# realSchematic.net
KiCad netlist of a schematic drawn in Altium Designer
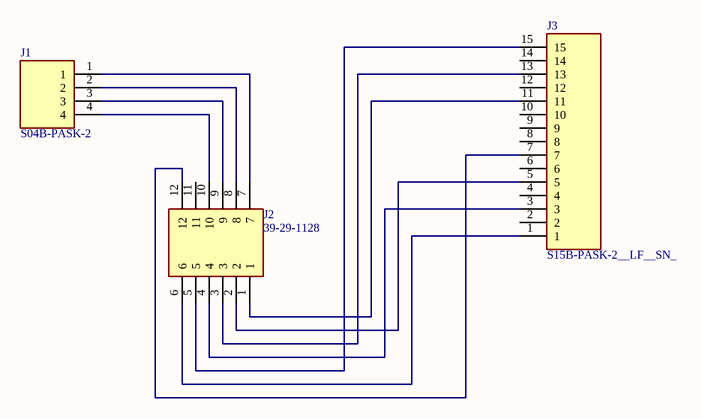
[diagram p0: realSchematic.SchDoc]

(export (version "E")
  (design (tool "Eeschema 10.0.6"))
  (components
    (comp (ref "J1")
      (value "S04B-PASK-2")
      (footprint "SamacSys:S04BPASK2")
      (description "Connector")
      (libsource (lib "*") (part "S04B-PASK-2"))
    )
    (comp (ref "J2")
      (value "39-29-1128")
      (footprint "SamacSys:39291128")
      (description "Connector")
      (fields (field (name "MOUSER PART NUMBER") "538-39-29-1128"))
      (libsource (lib "*") (part "39-29-1128"))
    )
    (comp (ref "J3")
      (value "S15B-PASK-2__LF__SN_")
      (footprint "SamacSys:S15BPASK2LFSN")
      (description "Connector")
      (fields (field (name "MANUFACTURER_PART_NUMBER") "S15B-PASK-2 (LF)(SN)"))
      (libsource (lib "*") (part "S15B-PASK-2__LF__SN_"))
    )
  )
  (nets
    (net (code "1") (name "Net-(J1-Pad1)") (class "Default")
      (node (ref "J1") (pin "1") (pinfunction "1_1") (pintype "passive"))
      (node (ref "J2") (pin "7") (pinfunction "7_7") (pintype "passive"))
    )
    (net (code "2") (name "Net-(J1-Pad2)") (class "Default")
      (node (ref "J1") (pin "2") (pinfunction "2_2") (pintype "passive"))
      (node (ref "J2") (pin "8") (pinfunction "8_8") (pintype "passive"))
    )
    (net (code "3") (name "Net-(J1-Pad3)") (class "Default")
      (node (ref "J1") (pin "3") (pinfunction "3_3") (pintype "passive"))
      (node (ref "J2") (pin "9") (pinfunction "9_9") (pintype "passive"))
    )
    (net (code "4") (name "Net-(J1-Pad4)") (class "Default")
      (node (ref "J1") (pin "4") (pinfunction "4_4") (pintype "passive"))
      (node (ref "J2") (pin "10") (pinfunction "10_10") (pintype "passive"))
    )
    (net (code "5") (name "Net-(J2-Pad1)") (class "Default")
      (node (ref "J2") (pin "1") (pinfunction "1_1") (pintype "passive"))
      (node (ref "J3") (pin "11") (pinfunction "11_11") (pintype "passive"))
    )
    (net (code "6") (name "Net-(J2-Pad2)") (class "Default")
      (node (ref "J2") (pin "2") (pinfunction "2_2") (pintype "passive"))
      (node (ref "J3") (pin "5") (pinfunction "5_5") (pintype "passive"))
    )
    (net (code "7") (name "Net-(J2-Pad3)") (class "Default")
      (node (ref "J2") (pin "3") (pinfunction "3_3") (pintype "passive"))
      (node (ref "J3") (pin "13") (pinfunction "13_13") (pintype "passive"))
    )
    (net (code "8") (name "Net-(J2-Pad4)") (class "Default")
      (node (ref "J2") (pin "4") (pinfunction "4_4") (pintype "passive"))
      (node (ref "J3") (pin "3") (pinfunction "3_3") (pintype "passive"))
    )
    (net (code "9") (name "Net-(J2-Pad5)") (class "Default")
      (node (ref "J2") (pin "5") (pinfunction "5_5") (pintype "passive"))
      (node (ref "J3") (pin "15") (pinfunction "15_15") (pintype "passive"))
    )
    (net (code "10") (name "Net-(J2-Pad6)") (class "Default")
      (node (ref "J2") (pin "6") (pinfunction "6_6") (pintype "passive"))
      (node (ref "J3") (pin "1") (pinfunction "1_1") (pintype "passive"))
    )
    (net (code "11") (name "Net-(J2-Pad12)") (class "Default")
      (node (ref "J2") (pin "12") (pinfunction "12_12") (pintype "passive"))
      (node (ref "J3") (pin "7") (pinfunction "7_7") (pintype "passive"))
    )
    (net (code "12") (name "unconnected-(J2-Pad11)") (class "Default")
      (node (ref "J2") (pin "11") (pinfunction "11_11") (pintype "passive"))
    )
    (net (code "13") (name "unconnected-(J3-Pad2)") (class "Default")
      (node (ref "J3") (pin "2") (pinfunction "2_2") (pintype "passive"))
    )
    (net (code "14") (name "unconnected-(J3-Pad4)") (class "Default")
      (node (ref "J3") (pin "4") (pinfunction "4_4") (pintype "passive"))
    )
    (net (code "15") (name "unconnected-(J3-Pad6)") (class "Default")
      (node (ref "J3") (pin "6") (pinfunction "6_6") (pintype "passive"))
    )
    (net (code "16") (name "unconnected-(J3-Pad8)") (class "Default")
      (node (ref "J3") (pin "8") (pinfunction "8_8") (pintype "passive"))
    )
    (net (code "17") (name "unconnected-(J3-Pad9)") (class "Default")
      (node (ref "J3") (pin "9") (pinfunction "9_9") (pintype "passive"))
    )
    (net (code "18") (name "unconnected-(J3-Pad10)") (class "Default")
      (node (ref "J3") (pin "10") (pinfunction "10_10") (pintype "passive"))
    )
    (net (code "19") (name "unconnected-(J3-Pad12)") (class "Default")
      (node (ref "J3") (pin "12") (pinfunction "12_12") (pintype "passive"))
    )
    (net (code "20") (name "unconnected-(J3-Pad14)") (class "Default")
      (node (ref "J3") (pin "14") (pinfunction "14_14") (pintype "passive"))
    )
  )
)
